# smartstand-headphone-detection-rev-c.net
KiCad netlist of a schematic drawn in EAGLE
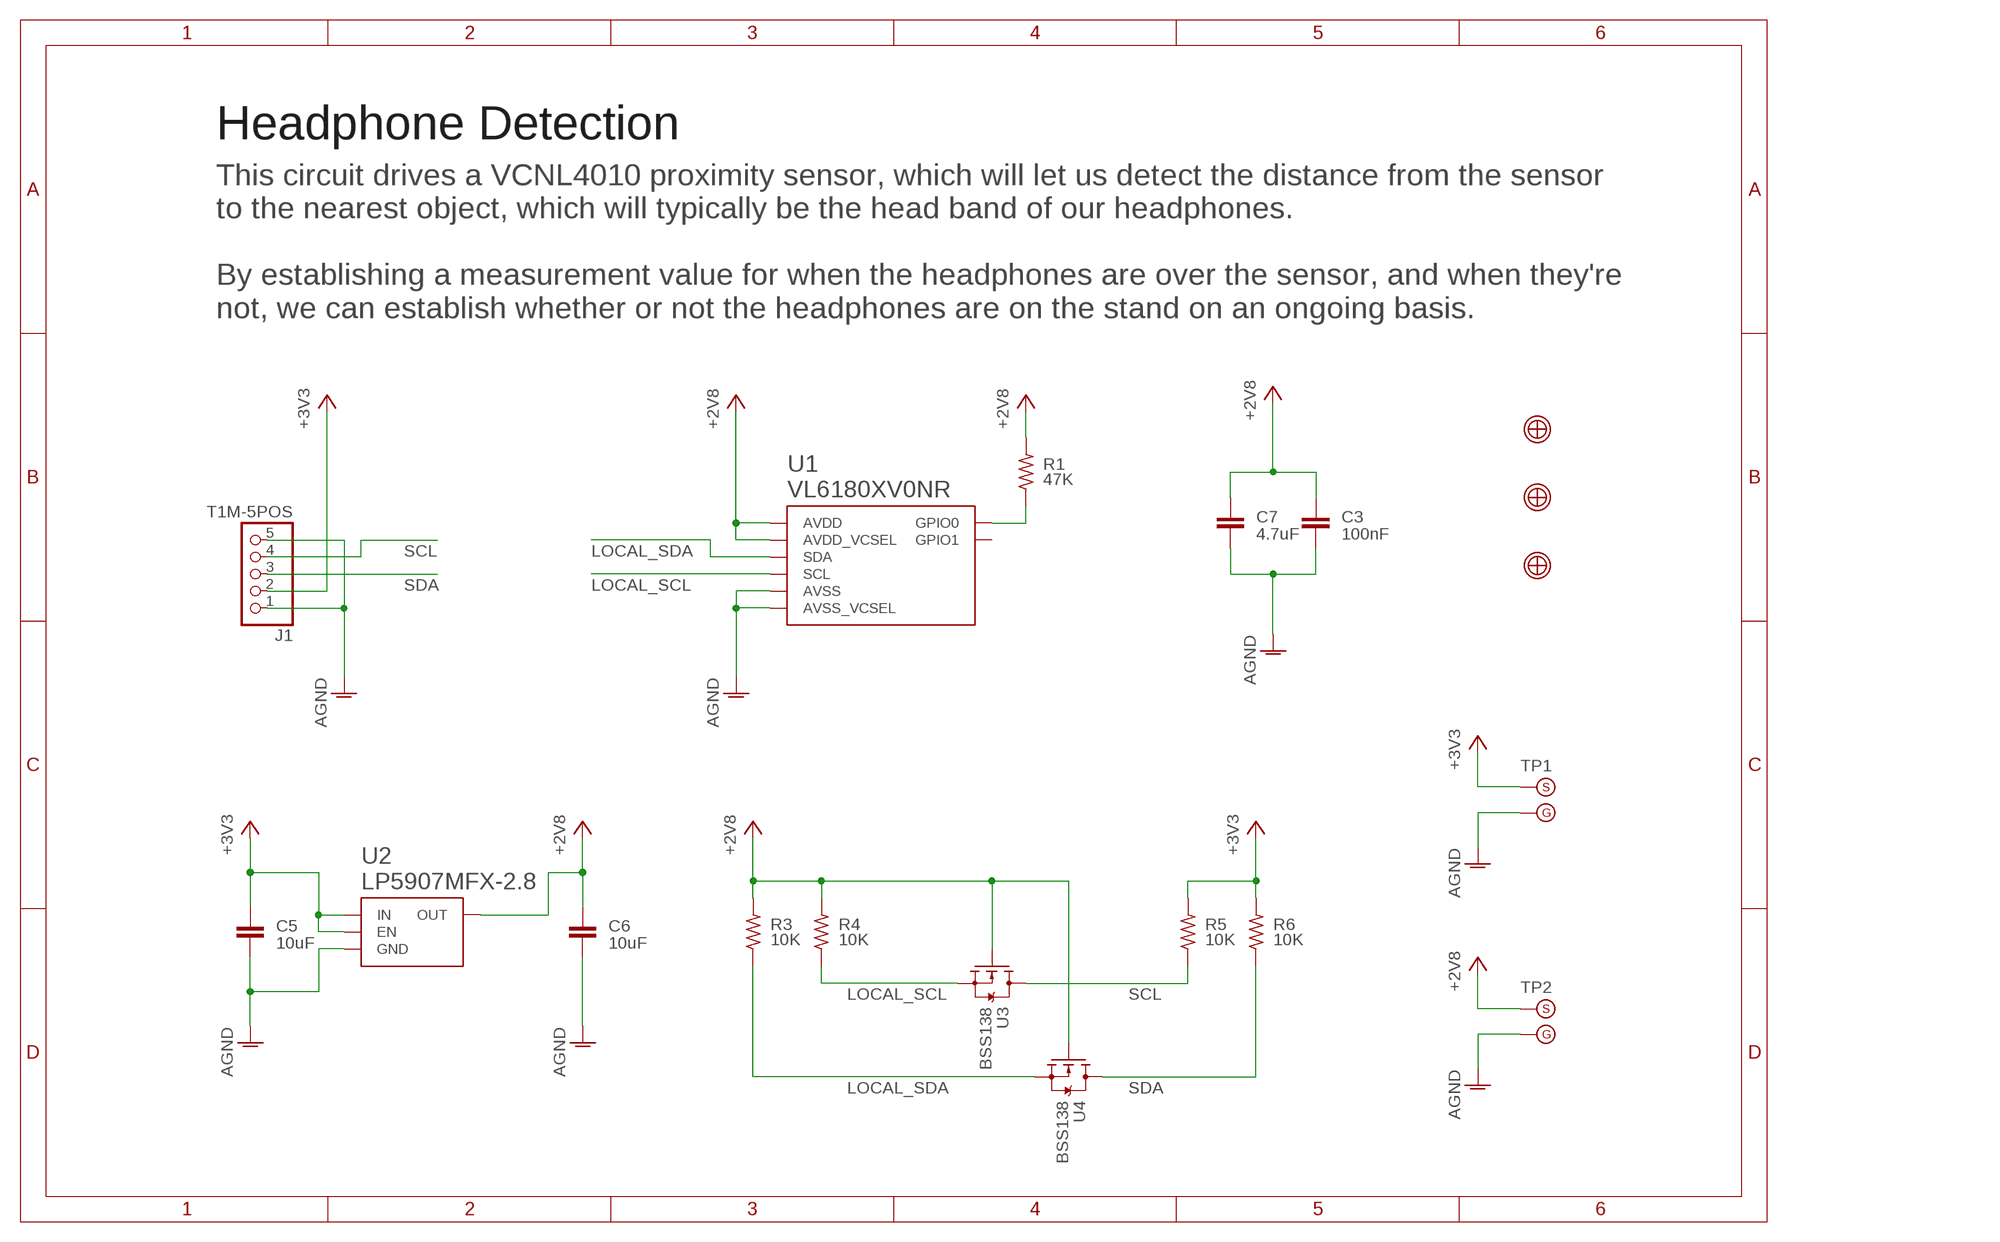
[diagram p0: schematic, sheet 1]

(export (version "E")
  (design (tool "Eeschema 10.0.6"))
  (components
    (comp (ref "C3")
      (value "100nF")
      (footprint "eagle-import:C0402")
      (libsource (lib "eagle-import") (part "CAPACITOR-0402"))
    )
    (comp (ref "C5")
      (value "10uF")
      (footprint "eagle-import:C0603")
      (libsource (lib "eagle-import") (part "CAPACITOR-0603"))
    )
    (comp (ref "C6")
      (value "10uF")
      (footprint "eagle-import:C0603")
      (libsource (lib "eagle-import") (part "CAPACITOR-0603"))
    )
    (comp (ref "C7")
      (value "4.7uF")
      (footprint "eagle-import:C0603")
      (libsource (lib "eagle-import") (part "CAPACITOR-0603"))
    )
    (comp (ref "J1")
      (value "T1M-5POS")
      (footprint "eagle-import:T1M-SINGLE-5POS")
      (libsource (lib "eagle-import") (part "T1M-5POS"))
    )
    (comp (ref "R1")
      (value "47K")
      (footprint "eagle-import:R0402")
      (libsource (lib "eagle-import") (part "RESISTOR-0402"))
    )
    (comp (ref "R3")
      (value "10K")
      (footprint "eagle-import:R0402")
      (libsource (lib "eagle-import") (part "RESISTOR-0402"))
    )
    (comp (ref "R4")
      (value "10K")
      (footprint "eagle-import:R0402")
      (libsource (lib "eagle-import") (part "RESISTOR-0402"))
    )
    (comp (ref "R5")
      (value "10K")
      (footprint "eagle-import:R0402")
      (libsource (lib "eagle-import") (part "RESISTOR-0402"))
    )
    (comp (ref "R6")
      (value "10K")
      (footprint "eagle-import:R0402")
      (libsource (lib "eagle-import") (part "RESISTOR-0402"))
    )
    (comp (ref "TP1")
      (value "TESTPOINT-WITH-GND")
      (footprint "eagle-import:TESTPOINT-1.5-WITH-GND")
      (libsource (lib "eagle-import") (part "TESTPOINT-WITH-GND"))
    )
    (comp (ref "TP2")
      (value "TESTPOINT-WITH-GND")
      (footprint "eagle-import:TESTPOINT-1.5-WITH-GND")
      (libsource (lib "eagle-import") (part "TESTPOINT-WITH-GND"))
    )
    (comp (ref "U$1")
      (value "FIDUCIAL-1MM")
      (footprint "eagle-import:FIDUCIAL_1MM")
      (libsource (lib "eagle-import") (part "FIDUCIAL-1MM"))
    )
    (comp (ref "U$2")
      (value "FIDUCIAL-1MM")
      (footprint "eagle-import:FIDUCIAL_1MM")
      (libsource (lib "eagle-import") (part "FIDUCIAL-1MM"))
    )
    (comp (ref "U$3")
      (value "FIDUCIAL-1MM")
      (footprint "eagle-import:FIDUCIAL_1MM")
      (libsource (lib "eagle-import") (part "FIDUCIAL-1MM"))
    )
    (comp (ref "U1")
      (value "VL6180XV0NR")
      (footprint "eagle-import:VL6180X")
      (libsource (lib "eagle-import") (part "VL6180XV0NR"))
    )
    (comp (ref "U2")
      (value "LP5907MFX-2.8")
      (footprint "eagle-import:R-PDSO-G5-DBV")
      (libsource (lib "eagle-import") (part "LP5907MFX-2.8"))
    )
    (comp (ref "U3")
      (value "BSS138")
      (footprint "eagle-import:SOT23")
      (libsource (lib "eagle-import") (part "BSS138LT3G"))
    )
    (comp (ref "U4")
      (value "BSS138")
      (footprint "eagle-import:SOT23")
      (libsource (lib "eagle-import") (part "BSS138LT3G"))
    )
  )
  (nets
    (net (code "1") (name "+2V8") (class "Default")
      (node (ref "C3") (pin "1") (pinfunction "1_1") (pintype "passive"))
      (node (ref "C6") (pin "1") (pinfunction "1_1") (pintype "passive"))
      (node (ref "C7") (pin "1") (pinfunction "1_1") (pintype "passive"))
      (node (ref "R1") (pin "2") (pinfunction "2_2") (pintype "passive"))
      (node (ref "R3") (pin "2") (pinfunction "2_2") (pintype "passive"))
      (node (ref "R4") (pin "2") (pinfunction "2_2") (pintype "passive"))
      (node (ref "TP2") (pin "S") (pinfunction "S_S") (pintype "bidirectional"))
      (node (ref "U1") (pin "10") (pinfunction "AVDD_10") (pintype "bidirectional"))
      (node (ref "U1") (pin "8") (pinfunction "AVDD_VCSEL_8") (pintype "bidirectional"))
      (node (ref "U2") (pin "5") (pinfunction "OUT_5") (pintype "bidirectional"))
      (node (ref "U3") (pin "1") (pinfunction "G_1") (pintype "passive"))
      (node (ref "U4") (pin "1") (pinfunction "G_1") (pintype "passive"))
    )
    (net (code "2") (name "+3V3") (class "Default")
      (node (ref "C5") (pin "1") (pinfunction "1_1") (pintype "passive"))
      (node (ref "J1") (pin "2") (pinfunction "2_2") (pintype "passive"))
      (node (ref "R5") (pin "2") (pinfunction "2_2") (pintype "passive"))
      (node (ref "R6") (pin "2") (pinfunction "2_2") (pintype "passive"))
      (node (ref "TP1") (pin "S") (pinfunction "S_S") (pintype "bidirectional"))
      (node (ref "U2") (pin "1") (pinfunction "IN_1") (pintype "bidirectional"))
      (node (ref "U2") (pin "3") (pinfunction "EN_3") (pintype "bidirectional"))
    )
    (net (code "3") (name "/LOCAL_SCL") (class "Default")
      (node (ref "R4") (pin "1") (pinfunction "1_1") (pintype "passive"))
      (node (ref "U1") (pin "5") (pinfunction "SCL_5") (pintype "bidirectional"))
      (node (ref "U3") (pin "2") (pinfunction "S_2") (pintype "passive"))
    )
    (net (code "4") (name "/LOCAL_SDA") (class "Default")
      (node (ref "R3") (pin "1") (pinfunction "1_1") (pintype "passive"))
      (node (ref "U1") (pin "6") (pinfunction "SDA_6") (pintype "bidirectional"))
      (node (ref "U4") (pin "2") (pinfunction "S_2") (pintype "passive"))
    )
    (net (code "5") (name "/SCL") (class "Default")
      (node (ref "J1") (pin "4") (pinfunction "4_4") (pintype "passive"))
      (node (ref "R5") (pin "1") (pinfunction "1_1") (pintype "passive"))
      (node (ref "U3") (pin "3") (pinfunction "D_3") (pintype "passive"))
    )
    (net (code "6") (name "/SDA") (class "Default")
      (node (ref "J1") (pin "3") (pinfunction "3_3") (pintype "passive"))
      (node (ref "R6") (pin "1") (pinfunction "1_1") (pintype "passive"))
      (node (ref "U4") (pin "3") (pinfunction "D_3") (pintype "passive"))
    )
    (net (code "7") (name "AGND") (class "Default")
      (node (ref "C3") (pin "2") (pinfunction "2_2") (pintype "passive"))
      (node (ref "C5") (pin "2") (pinfunction "2_2") (pintype "passive"))
      (node (ref "C6") (pin "2") (pinfunction "2_2") (pintype "passive"))
      (node (ref "C7") (pin "2") (pinfunction "2_2") (pintype "passive"))
      (node (ref "J1") (pin "1") (pinfunction "1_1") (pintype "passive"))
      (node (ref "J1") (pin "5") (pinfunction "5_5") (pintype "passive"))
      (node (ref "TP1") (pin "G") (pinfunction "G_G") (pintype "bidirectional"))
      (node (ref "TP2") (pin "G") (pinfunction "G_G") (pintype "bidirectional"))
      (node (ref "U1") (pin "12") (pinfunction "AVSS_12") (pintype "bidirectional"))
      (node (ref "U1") (pin "9") (pinfunction "AVSS_VCSEL_9") (pintype "bidirectional"))
      (node (ref "U2") (pin "2") (pinfunction "GND_2") (pintype "bidirectional"))
    )
    (net (code "8") (name "Net-(U1-GPIO0)") (class "Default")
      (node (ref "R1") (pin "1") (pinfunction "1_1") (pintype "passive"))
      (node (ref "U1") (pin "4") (pinfunction "GPIO0_4") (pintype "bidirectional"))
    )
    (net (code "9") (name "unconnected-(U1-GPIO1-Pad1)") (class "Default")
      (node (ref "U1") (pin "1") (pinfunction "GPIO1_1") (pintype "bidirectional"))
    )
  )
)
